# Page1.net
KiCad netlist of a schematic drawn in Altium Designer
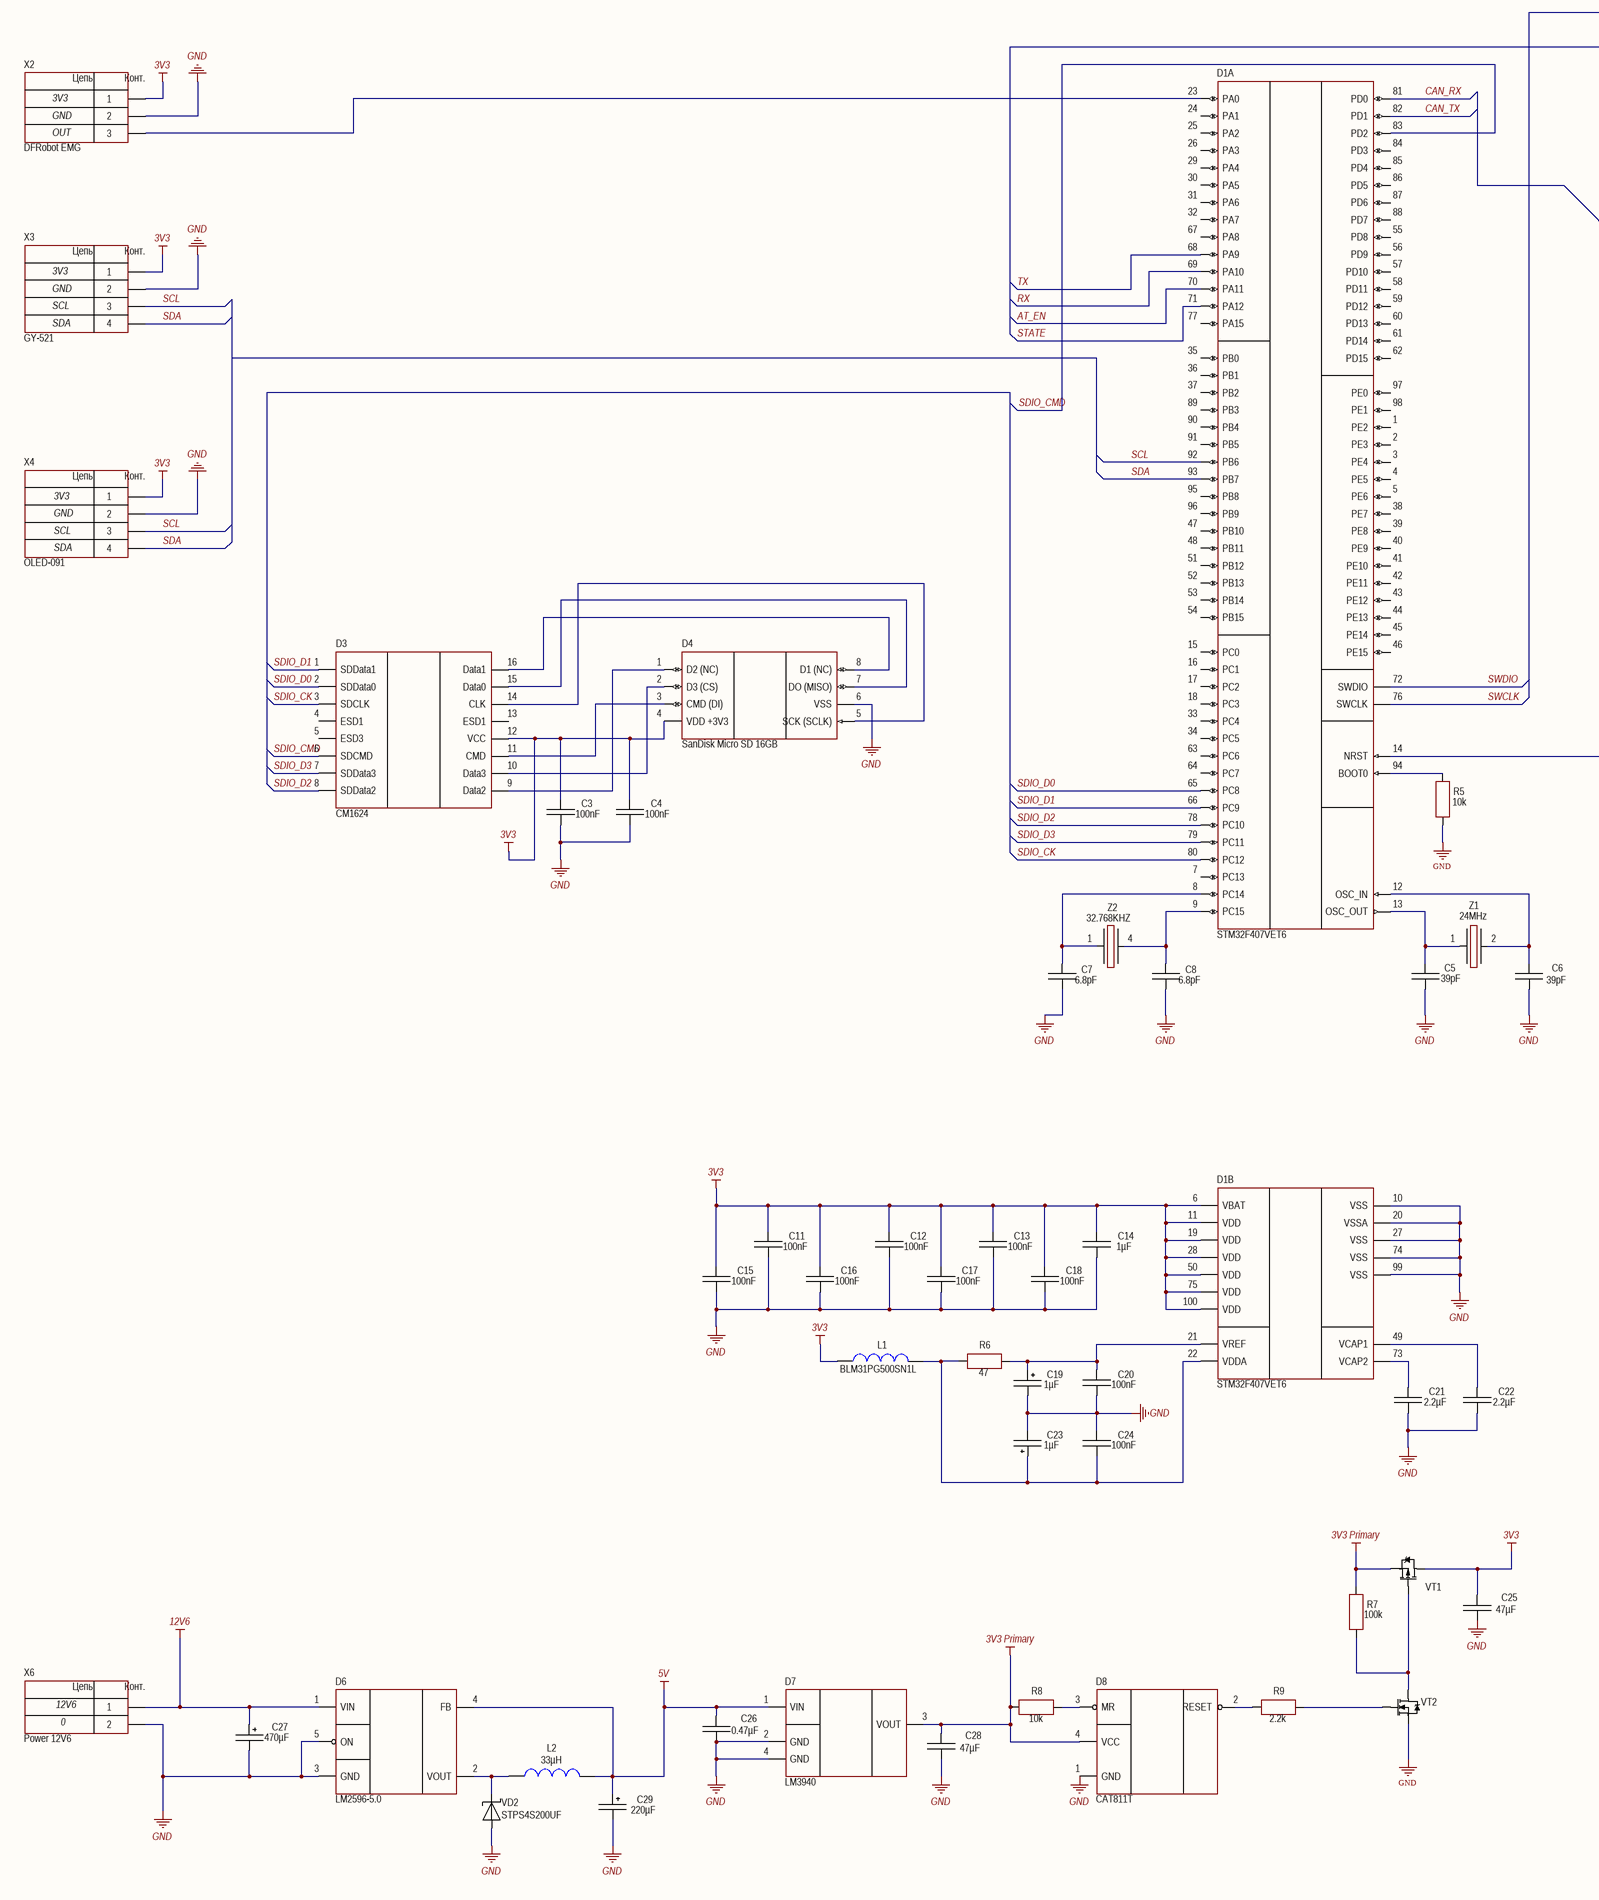
[diagram p0: Page1.SchDoc, left]
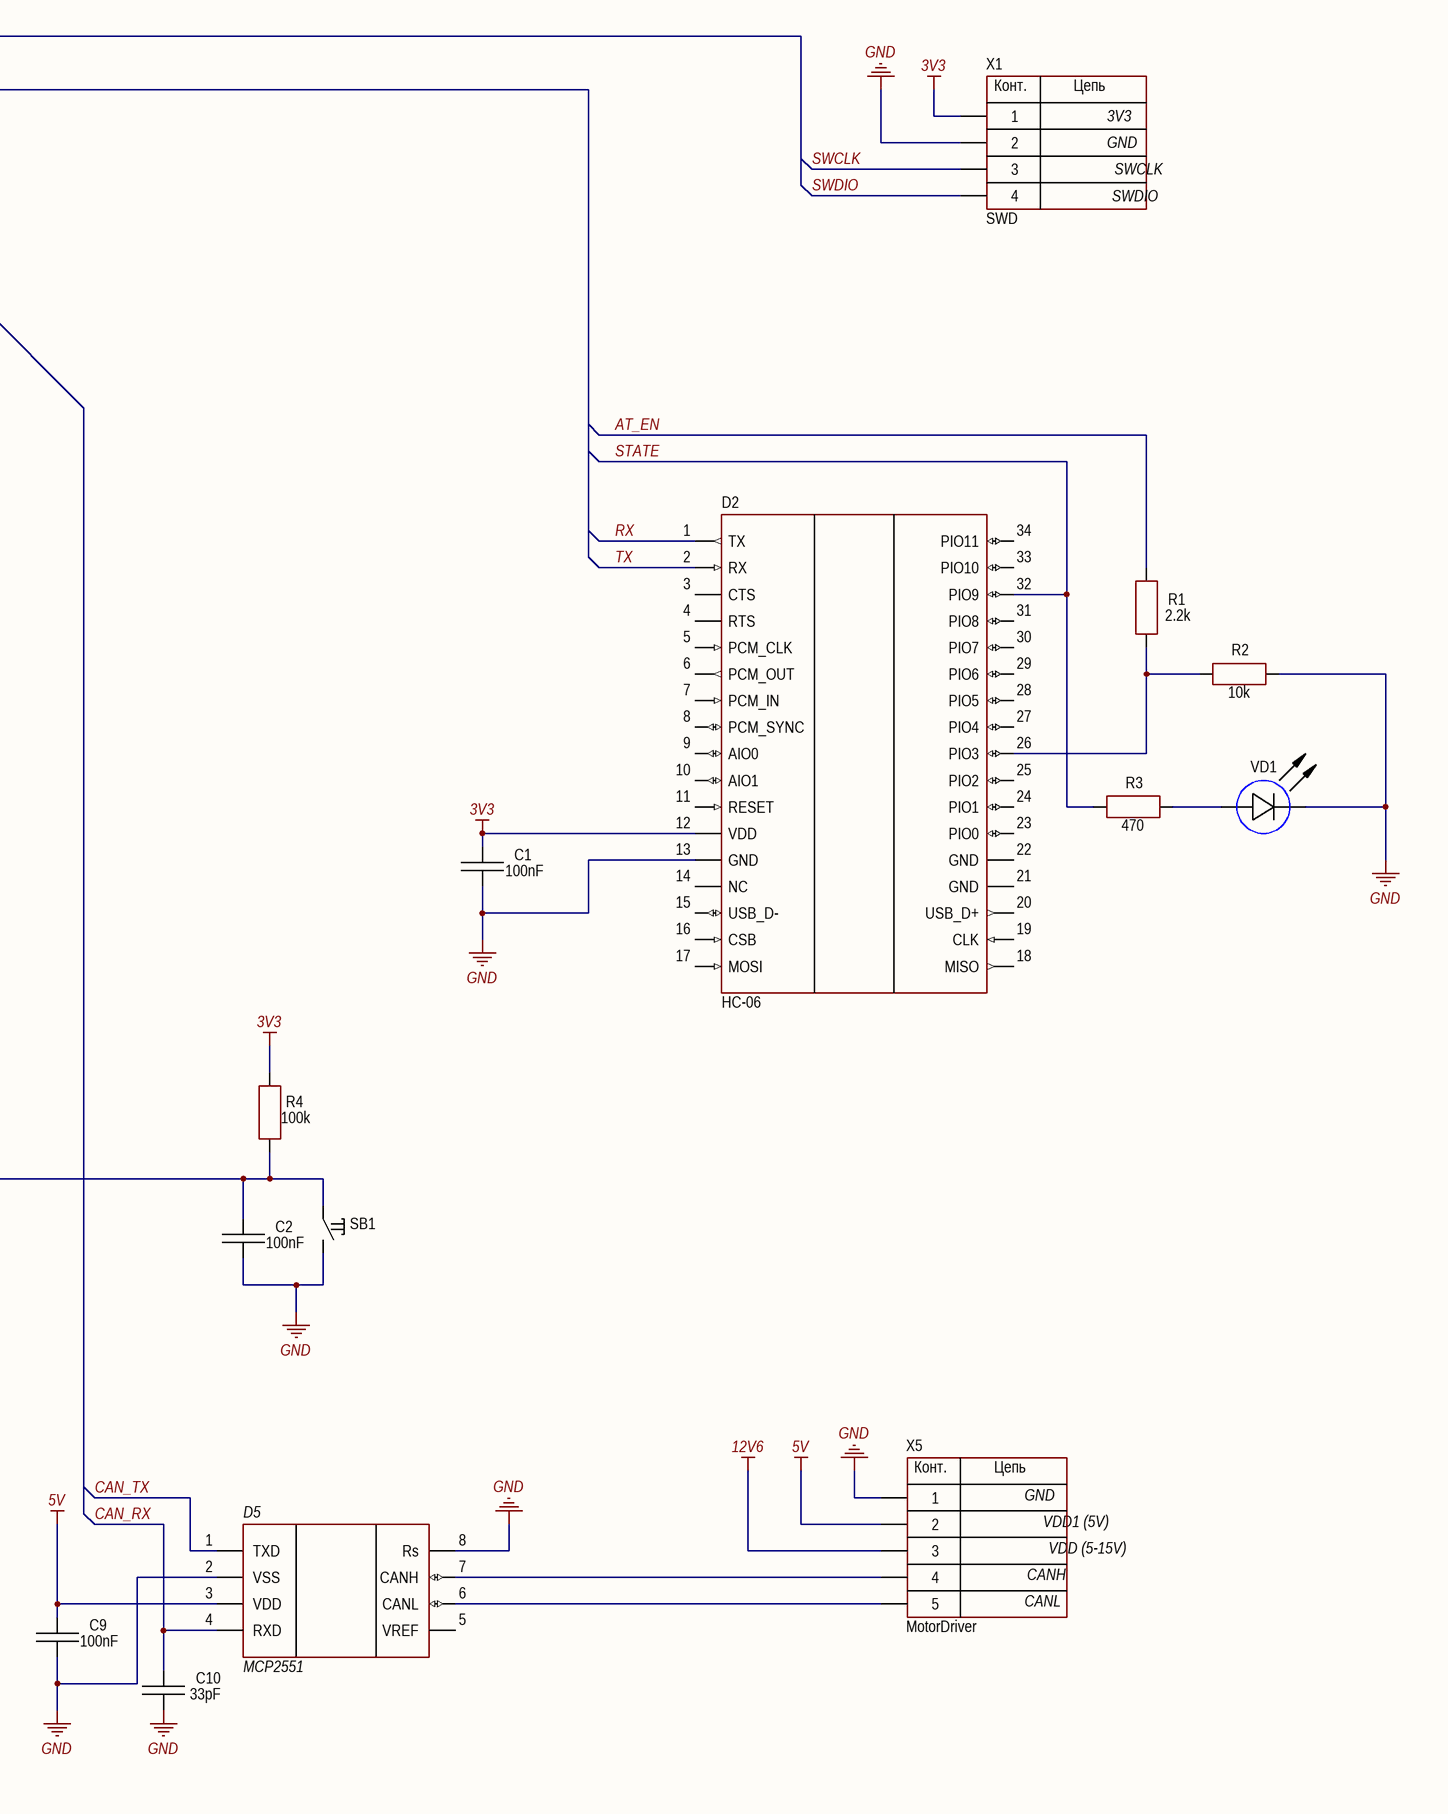
[diagram p1: Page1.SchDoc, right]

(export (version "E")
  (design (tool "Eeschema 10.0.6"))
  (components
    (comp (ref "C1")
      (value "100nF")
      (footprint "CH1206C")
      (fields (field (name "MANUFACTURER") "Murata Electronics North America"))
      (libsource (lib "Discrete") (part "Capacitor"))
    )
    (comp (ref "C2")
      (value "100nF")
      (footprint "CH1206C")
      (fields (field (name "MANUFACTURER") "Murata Electronics North America"))
      (libsource (lib "Discrete") (part "Capacitor"))
    )
    (comp (ref "C3")
      (value "100nF")
      (footprint "CH1206C")
      (fields (field (name "MANUFACTURER") "Murata Electronics North America"))
      (libsource (lib "Discrete") (part "Capacitor"))
    )
    (comp (ref "C4")
      (value "100nF")
      (footprint "CH1206C")
      (fields (field (name "MANUFACTURER") "Murata Electronics North America"))
      (libsource (lib "Discrete") (part "Capacitor"))
    )
    (comp (ref "C5")
      (value "39pF")
      (footprint "CH1206C")
      (fields (field (name "MANUFACTURER") "Murata Electronics North America"))
      (libsource (lib "Discrete") (part "Capacitor"))
    )
    (comp (ref "C6")
      (value "39pF")
      (footprint "CH1206C")
      (fields (field (name "MANUFACTURER") "Murata Electronics North America"))
      (libsource (lib "Discrete") (part "Capacitor"))
    )
    (comp (ref "C7")
      (value "6.8pF")
      (footprint "CH1206C")
      (fields (field (name "MANUFACTURER") "Wurth Electronics Inc."))
      (libsource (lib "Discrete") (part "Capacitor"))
    )
    (comp (ref "C8")
      (value "6.8pF")
      (footprint "CH1206C")
      (fields (field (name "MANUFACTURER") "Wurth Electronics Inc."))
      (libsource (lib "Discrete") (part "Capacitor"))
    )
    (comp (ref "C9")
      (value "100nF")
      (footprint "CH1206C")
      (fields (field (name "MANUFACTURER") "Murata Electronics North America"))
      (libsource (lib "Discrete") (part "Capacitor"))
    )
    (comp (ref "C10")
      (value "33pF")
      (footprint "CH1206C")
      (fields (field (name "MANUFACTURER") "Murata Electronics North America"))
      (libsource (lib "Discrete") (part "Capacitor"))
    )
    (comp (ref "C11")
      (value "100nF")
      (footprint "CH1206C")
      (fields (field (name "MANUFACTURER") "Murata Electronics North America"))
      (libsource (lib "Discrete") (part "Capacitor"))
    )
    (comp (ref "C12")
      (value "100nF")
      (footprint "CH1206C")
      (fields (field (name "MANUFACTURER") "Murata Electronics North America"))
      (libsource (lib "Discrete") (part "Capacitor"))
    )
    (comp (ref "C13")
      (value "100nF")
      (footprint "CH1206C")
      (fields (field (name "MANUFACTURER") "Murata Electronics North America"))
      (libsource (lib "Discrete") (part "Capacitor"))
    )
    (comp (ref "C14")
      (value "1µF")
      (footprint "CH1206C")
      (fields (field (name "MANUFACTURER") "Murata Electronics North America"))
      (libsource (lib "Discrete") (part "Capacitor"))
    )
    (comp (ref "C15")
      (value "100nF")
      (footprint "CH1206C")
      (fields (field (name "MANUFACTURER") "Murata Electronics North America"))
      (libsource (lib "Discrete") (part "Capacitor"))
    )
    (comp (ref "C16")
      (value "100nF")
      (footprint "CH1206C")
      (fields (field (name "MANUFACTURER") "Murata Electronics North America"))
      (libsource (lib "Discrete") (part "Capacitor"))
    )
    (comp (ref "C17")
      (value "100nF")
      (footprint "CH1206C")
      (fields (field (name "MANUFACTURER") "Murata Electronics North America"))
      (libsource (lib "Discrete") (part "Capacitor"))
    )
    (comp (ref "C18")
      (value "100nF")
      (footprint "CH1206C")
      (fields (field (name "MANUFACTURER") "Murata Electronics North America"))
      (libsource (lib "Discrete") (part "Capacitor"))
    )
    (comp (ref "C19")
      (value "1µF")
      (footprint "CAP: Alchip™- MVY")
      (fields (field (name "MANUFACTURER") "United Chemi-Con"))
      (libsource (lib "Discrete") (part "AlumCap"))
    )
    (comp (ref "C20")
      (value "100nF")
      (footprint "CH1206C")
      (fields (field (name "MANUFACTURER") "Murata Electronics North America"))
      (libsource (lib "Discrete") (part "Capacitor"))
    )
    (comp (ref "C21")
      (value "2.2µF")
      (footprint "CH1206C")
      (fields (field (name "MANUFACTURER") "Murata Electronics North America"))
      (libsource (lib "Discrete") (part "Capacitor"))
    )
    (comp (ref "C22")
      (value "2.2µF")
      (footprint "CH1206C")
      (fields (field (name "MANUFACTURER") "Murata Electronics North America"))
      (libsource (lib "Discrete") (part "Capacitor"))
    )
    (comp (ref "C23")
      (value "1µF")
      (footprint "CAP: Alchip™- MVY")
      (fields (field (name "MANUFACTURER") "United Chemi-Con"))
      (libsource (lib "Discrete") (part "AlumCap"))
    )
    (comp (ref "C24")
      (value "100nF")
      (footprint "CH1206C")
      (fields (field (name "MANUFACTURER") "Murata Electronics North America"))
      (libsource (lib "Discrete") (part "Capacitor"))
    )
    (comp (ref "C25")
      (value "47µF")
      (footprint "CH1206C")
      (fields (field (name "MANUFACTURER") "Murata Electronics North America"))
      (libsource (lib "Discrete") (part "Capacitor"))
    )
    (comp (ref "C26")
      (value "0.47µF")
      (footprint "CH1206C")
      (fields (field (name "MANUFACTURER") "Wurth Electronics Inc."))
      (libsource (lib "Discrete") (part "Capacitor"))
    )
    (comp (ref "C27")
      (value "470µF")
      (footprint "CAP: Alchip™- MVY")
      (fields (field (name "MANUFACTURER") "United Chemi-Con"))
      (libsource (lib "Discrete") (part "AlumCap"))
    )
    (comp (ref "C28")
      (value "47µF")
      (footprint "CH1206C")
      (fields (field (name "MANUFACTURER") "Murata Electronics North America"))
      (libsource (lib "Discrete") (part "Capacitor"))
    )
    (comp (ref "C29")
      (value "220µF")
      (footprint "CAP: Alchip™- MVY")
      (fields (field (name "MANUFACTURER") "United Chemi-Con"))
      (libsource (lib "Discrete") (part "AlumCap"))
    )
    (comp (ref "D1")
      (value "STM32F407VET6")
      (footprint "100-LQFP")
      (description "Cortex-M4")
      (fields (field (name "MANUFACTURER") "STMicroelectronics"))
      (libsource (lib "Digital") (part "STM32F407VET6"))
    )
    (comp (ref "D2")
      (value "HC-06")
      (footprint "MOD: HC-05")
      (description "Bluetooth")
      (fields (field (name "MANUFACTURER") "China"))
      (libsource (lib "Module") (part "HC-06"))
    )
    (comp (ref "D3")
      (value "CM1624")
      (description "EMI Filter for T-Flash")
      (fields (field (name "MANUFACTURER") "ON Semiconductor"))
      (libsource (lib "Power Supplies") (part "CM1624"))
    )
    (comp (ref "D4")
      (value "SanDisk Micro SD 16GB")
      (description "Flash")
      (fields (field (name "MANUFACTURER") "SanDisk"))
      (libsource (lib "Digital") (part "MicroSD"))
    )
    (comp (ref "D5")
      (value "MCP2551")
      (footprint "SOT23-8")
      (description "CAN Transceiver")
      (fields (field (name "MANUFACTURER") "China"))
      (libsource (lib "Digital") (part "MCP2551"))
    )
    (comp (ref "D6")
      (value "LM2596-5.0")
      (footprint "D2PAK-5")
      (description "LDO")
      (fields (field (name "MANUFACTURER") "ON Semiconductor"))
      (libsource (lib "Power Supplies") (part "LM2596"))
    )
    (comp (ref "D7")
      (value "LM3940")
      (footprint "SOT223")
      (description "LDO")
      (libsource (lib "Power Supplies") (part "LM3940"))
    )
    (comp (ref "D8")
      (value "CAT811T")
      (description "Power Supply Supervisor")
      (fields (field (name "MANUFACTURER") "ON Semiconductor"))
      (libsource (lib "Power Supplies") (part "CAT811T"))
    )
    (comp (ref "L1")
      (value "BLM31PG500SN1L")
      (footprint "C1206")
      (fields (field (name "MANUFACTURER") "Murata Electronics North America"))
      (libsource (lib "Discrete") (part "Inductor"))
    )
    (comp (ref "L2")
      (value "33µH")
      (footprint "IND: CDRH127")
      (fields (field (name "MANUFACTURER") "Wurth Electronics Inc."))
      (libsource (lib "Discrete") (part "Inductor"))
    )
    (comp (ref "R1")
      (value "2.2k")
      (footprint "CH1206R")
      (fields (field (name "MANUFACTURER") "Panasonic Electronic Components"))
      (libsource (lib "Discrete") (part "Resistor"))
    )
    (comp (ref "R2")
      (value "10k")
      (footprint "CH1206R")
      (fields (field (name "MANUFACTURER") "Stackpole Electronics Inc"))
      (libsource (lib "") (part "Resistor_1"))
    )
    (comp (ref "R3")
      (value "470")
      (footprint "CH1206R")
      (fields (field (name "MANUFACTURER") "Stackpole Electronics Inc"))
      (libsource (lib "") (part "Resistor_1"))
    )
    (comp (ref "R4")
      (value "100k")
      (footprint "CH1206R")
      (fields (field (name "MANUFACTURER") "Stackpole Electronics Inc"))
      (libsource (lib "Discrete") (part "Resistor"))
    )
    (comp (ref "R5")
      (value "10k")
      (footprint "CH0201R")
      (fields (field (name "MANUFACTURER") "Stackpole Electronics Inc"))
      (libsource (lib "Discrete") (part "Resistor"))
    )
    (comp (ref "R6")
      (value "47")
      (footprint "CH1206R")
      (fields (field (name "MANUFACTURER") "Stackpole Electronics Inc"))
      (libsource (lib "") (part "Resistor_1"))
    )
    (comp (ref "R7")
      (value "100k")
      (footprint "CH0201R")
      (fields (field (name "MANUFACTURER") "Stackpole Electronics Inc"))
      (libsource (lib "Discrete") (part "Resistor"))
    )
    (comp (ref "R8")
      (value "10k")
      (footprint "CH0201R")
      (fields (field (name "MANUFACTURER") "Stackpole Electronics Inc"))
      (libsource (lib "") (part "Resistor_1"))
    )
    (comp (ref "R9")
      (value "2.2k")
      (footprint "CH0201R")
      (fields (field (name "MANUFACTURER") "Panasonic Electronic Components"))
      (libsource (lib "") (part "Resistor_1"))
    )
    (comp (ref "SB1")
      (value "~")
      (footprint "BUT: 6x6")
      (description "6x6 mm")
      (fields (field (name "MANUFACTURER") "C&K"))
      (libsource (lib "Connectors") (part "Tactile switches"))
    )
    (comp (ref "VD1")
      (value "~")
      (footprint "CH1206LG")
      (fields (field (name "MANUFACTURER") "QT Brightek (QTB)"))
      (libsource (lib "Discrete") (part "LED"))
    )
    (comp (ref "VD2")
      (value "STPS4S200UF")
      (footprint "DO221AA")
      (fields (field (name "MANUFACTURER") "STMicroelectronics"))
      (libsource (lib "Diods") (part "Diod Schottky"))
    )
    (comp (ref "VT1")
      (value "SI2329DS-T1-GE3")
      (footprint "SOT23_321")
      (description "Mosfet")
      (fields (field (name "MANUFACTURER") "Vishay Siliconix"))
      (libsource (lib "Transistor") (part "P-chanel"))
    )
    (comp (ref "VT2")
      (value "SI2342DS-T1-GE3")
      (footprint "SOT23_321")
      (description "Mosfet")
      (fields (field (name "MANUFACTURER") "Vishay Siliconix"))
      (libsource (lib "Transistor") (part "N-chanel"))
    )
    (comp (ref "X1")
      (value "SWD")
      (footprint "CON: 0533750410")
      (fields (field (name "MANUFACTURER") "Molex"))
      (libsource (lib "") (part "4-Connector_1"))
    )
    (comp (ref "X2")
      (value "DFRobot EMG")
      (footprint "CON: 0533750310")
      (fields (field (name "MANUFACTURER") "Molex"))
      (libsource (lib "Connectors") (part "3-Connector"))
    )
    (comp (ref "X3")
      (value "GY-521")
      (footprint "CON: 0533750410")
      (fields (field (name "MANUFACTURER") "Molex"))
      (libsource (lib "Connectors") (part "4-Connector"))
    )
    (comp (ref "X4")
      (value "OLED-091")
      (footprint "CON: 0533750410")
      (fields (field (name "MANUFACTURER") "Molex"))
      (libsource (lib "Connectors") (part "4-Connector"))
    )
    (comp (ref "X5")
      (value "MotorDriver")
      (footprint "CON: 0533750510")
      (fields (field (name "MANUFACTURER") "Molex"))
      (libsource (lib "Connectors") (part "5-Connector"))
    )
    (comp (ref "X6")
      (value "Power 12V6")
      (footprint "CON: 0533750210")
      (fields (field (name "MANUFACTURER") "Molex"))
      (libsource (lib "Connectors") (part "2-Connector"))
    )
    (comp (ref "Z1")
      (value "24MHz")
      (footprint "OSC: 5032")
      (fields (field (name "MANUFACTURER") "Abracon LLC"))
      (libsource (lib "") (part "Oscillator_1"))
    )
    (comp (ref "Z2")
      (value "32.768KHZ")
      (footprint "OSC: 2520")
      (fields (field (name "MANUFACTURER") "Epson Toyocom"))
      (libsource (lib "Discrete") (part "Oscillator"))
    )
  )
  (nets
    (net (code "1") (name "/AT_EN") (class "Default")
      (node (ref "D1") (pin "70") (pinfunction "PA11_70") (pintype "bidirectional"))
      (node (ref "R1") (pin "2") (pinfunction "2_2") (pintype "passive"))
    )
    (net (code "2") (name "/CAN_RX") (class "Default")
      (node (ref "C10") (pin "2") (pinfunction "2_2") (pintype "power_in"))
      (node (ref "D1") (pin "81") (pinfunction "PD0_81") (pintype "bidirectional"))
      (node (ref "D5") (pin "4") (pinfunction "RXD_4") (pintype "passive"))
    )
    (net (code "3") (name "/CAN_TX") (class "Default")
      (node (ref "D1") (pin "82") (pinfunction "PD1_82") (pintype "bidirectional"))
      (node (ref "D5") (pin "1") (pinfunction "TXD_1") (pintype "passive"))
    )
    (net (code "4") (name "/RX") (class "Default")
      (node (ref "D1") (pin "69") (pinfunction "PA10_69") (pintype "bidirectional"))
      (node (ref "D2") (pin "1") (pinfunction "TX_1") (pintype "output"))
    )
    (net (code "5") (name "/SCL") (class "Default")
      (node (ref "D1") (pin "92") (pinfunction "PB6_92") (pintype "bidirectional"))
      (node (ref "X3") (pin "3") (pinfunction "3_3") (pintype "power_in"))
      (node (ref "X4") (pin "3") (pinfunction "3_3") (pintype "power_in"))
    )
    (net (code "6") (name "/SDA") (class "Default")
      (node (ref "D1") (pin "93") (pinfunction "PB7_93") (pintype "bidirectional"))
      (node (ref "X3") (pin "4") (pinfunction "4_4") (pintype "power_in"))
      (node (ref "X4") (pin "4") (pinfunction "4_4") (pintype "power_in"))
    )
    (net (code "7") (name "/SDIO_CK") (class "Default")
      (node (ref "D1") (pin "80") (pinfunction "PC12_80") (pintype "bidirectional"))
      (node (ref "D3") (pin "3") (pinfunction "SDCLK_3") (pintype "passive"))
    )
    (net (code "8") (name "/SDIO_CMD") (class "Default")
      (node (ref "D1") (pin "83") (pinfunction "PD2_83") (pintype "bidirectional"))
      (node (ref "D3") (pin "6") (pinfunction "SDCMD_6") (pintype "passive"))
    )
    (net (code "9") (name "/SDIO_D0") (class "Default")
      (node (ref "D1") (pin "65") (pinfunction "PC8_65") (pintype "bidirectional"))
      (node (ref "D3") (pin "2") (pinfunction "SDData0_2") (pintype "passive"))
    )
    (net (code "10") (name "/SDIO_D1") (class "Default")
      (node (ref "D1") (pin "66") (pinfunction "PC9_66") (pintype "bidirectional"))
      (node (ref "D3") (pin "1") (pinfunction "SDData1_1") (pintype "passive"))
    )
    (net (code "11") (name "/SDIO_D2") (class "Default")
      (node (ref "D1") (pin "78") (pinfunction "PC10_78") (pintype "bidirectional"))
      (node (ref "D3") (pin "8") (pinfunction "SDData2_8") (pintype "passive"))
    )
    (net (code "12") (name "/SDIO_D3") (class "Default")
      (node (ref "D1") (pin "79") (pinfunction "PC11_79") (pintype "bidirectional"))
      (node (ref "D3") (pin "7") (pinfunction "SDData3_7") (pintype "passive"))
    )
    (net (code "13") (name "/STATE") (class "Default")
      (node (ref "D1") (pin "71") (pinfunction "PA12_71") (pintype "bidirectional"))
      (node (ref "D2") (pin "32") (pinfunction "PIO9_32") (pintype "bidirectional"))
      (node (ref "R3") (pin "1") (pinfunction "1_1") (pintype "passive"))
    )
    (net (code "14") (name "/SWCLK") (class "Default")
      (node (ref "D1") (pin "76") (pinfunction "SWCLK_76") (pintype "passive"))
      (node (ref "X1") (pin "3") (pinfunction "3_3") (pintype "power_in"))
    )
    (net (code "15") (name "/SWDIO") (class "Default")
      (node (ref "D1") (pin "72") (pinfunction "SWDIO_72") (pintype "passive"))
      (node (ref "X1") (pin "4") (pinfunction "4_4") (pintype "power_in"))
    )
    (net (code "16") (name "/TX") (class "Default")
      (node (ref "D1") (pin "68") (pinfunction "PA9_68") (pintype "bidirectional"))
      (node (ref "D2") (pin "2") (pinfunction "RX_2") (pintype "input"))
    )
    (net (code "17") (name "3V3") (class "Default")
      (node (ref "C1") (pin "2") (pinfunction "2_2") (pintype "power_in"))
      (node (ref "C11") (pin "2") (pinfunction "2_2") (pintype "power_in"))
      (node (ref "C12") (pin "2") (pinfunction "2_2") (pintype "power_in"))
      (node (ref "C13") (pin "2") (pinfunction "2_2") (pintype "power_in"))
      (node (ref "C14") (pin "2") (pinfunction "2_2") (pintype "power_in"))
      (node (ref "C15") (pin "2") (pinfunction "2_2") (pintype "power_in"))
      (node (ref "C16") (pin "2") (pinfunction "2_2") (pintype "power_in"))
      (node (ref "C17") (pin "2") (pinfunction "2_2") (pintype "power_in"))
      (node (ref "C18") (pin "2") (pinfunction "2_2") (pintype "power_in"))
      (node (ref "C25") (pin "1") (pinfunction "1_1") (pintype "power_in"))
      (node (ref "C3") (pin "2") (pinfunction "2_2") (pintype "power_in"))
      (node (ref "C4") (pin "2") (pinfunction "2_2") (pintype "power_in"))
      (node (ref "D1") (pin "100") (pinfunction "VDD_100") (pintype "power_in"))
      (node (ref "D1") (pin "11") (pinfunction "VDD_11") (pintype "power_in"))
      (node (ref "D1") (pin "19") (pinfunction "VDD_19") (pintype "power_in"))
      (node (ref "D1") (pin "28") (pinfunction "VDD_28") (pintype "power_in"))
      (node (ref "D1") (pin "50") (pinfunction "VDD_50") (pintype "power_in"))
      (node (ref "D1") (pin "6") (pinfunction "VBAT_6") (pintype "power_in"))
      (node (ref "D1") (pin "75") (pinfunction "VDD_75") (pintype "power_in"))
      (node (ref "D2") (pin "12") (pinfunction "VDD_12") (pintype "passive"))
      (node (ref "D3") (pin "12") (pinfunction "VCC_12") (pintype "passive"))
      (node (ref "D4") (pin "4") (pinfunction "VDD_+3V3_4") (pintype "power_in"))
      (node (ref "L1") (pin "2") (pinfunction "2_2") (pintype "passive"))
      (node (ref "R4") (pin "2") (pinfunction "2_2") (pintype "passive"))
      (node (ref "VT1") (pin "2") (pinfunction "D_2") (pintype "passive"))
      (node (ref "X1") (pin "1") (pinfunction "1_1") (pintype "passive"))
      (node (ref "X2") (pin "1") (pinfunction "1_1") (pintype "passive"))
      (node (ref "X3") (pin "1") (pinfunction "1_1") (pintype "passive"))
      (node (ref "X4") (pin "1") (pinfunction "1_1") (pintype "passive"))
    )
    (net (code "18") (name "3V3 Primary") (class "Default")
      (node (ref "C28") (pin "1") (pinfunction "1_1") (pintype "power_in"))
      (node (ref "D7") (pin "3") (pinfunction "VOUT_3") (pintype "power_in"))
      (node (ref "D8") (pin "4") (pinfunction "VCC_4") (pintype "power_in"))
      (node (ref "R7") (pin "2") (pinfunction "2_2") (pintype "passive"))
      (node (ref "R8") (pin "1") (pinfunction "1_1") (pintype "passive"))
      (node (ref "VT1") (pin "3") (pinfunction "S_3") (pintype "passive"))
    )
    (net (code "19") (name "5V") (class "Default")
      (node (ref "C26") (pin "1") (pinfunction "1_1") (pintype "power_in"))
      (node (ref "C29") (pin "1") (pinfunction "1_1") (pintype "power_in"))
      (node (ref "C9") (pin "2") (pinfunction "2_2") (pintype "power_in"))
      (node (ref "D5") (pin "3") (pinfunction "VDD_3") (pintype "power_in"))
      (node (ref "D6") (pin "4") (pinfunction "FB_4") (pintype "power_in"))
      (node (ref "D7") (pin "1") (pinfunction "VIN_1") (pintype "power_in"))
      (node (ref "L2") (pin "1") (pinfunction "1_1") (pintype "passive"))
      (node (ref "X5") (pin "2") (pinfunction "2_2") (pintype "passive"))
    )
    (net (code "20") (name "12V6") (class "Default")
      (node (ref "C27") (pin "1") (pinfunction "1_1") (pintype "power_in"))
      (node (ref "D6") (pin "1") (pinfunction "VIN_1") (pintype "power_in"))
      (node (ref "X5") (pin "3") (pinfunction "3_3") (pintype "power_in"))
      (node (ref "X6") (pin "1") (pinfunction "1_1") (pintype "passive"))
    )
    (net (code "21") (name "GND") (class "Default")
      (node (ref "C1") (pin "1") (pinfunction "1_1") (pintype "power_in"))
      (node (ref "C10") (pin "1") (pinfunction "1_1") (pintype "power_in"))
      (node (ref "C11") (pin "1") (pinfunction "1_1") (pintype "power_in"))
      (node (ref "C12") (pin "1") (pinfunction "1_1") (pintype "power_in"))
      (node (ref "C13") (pin "1") (pinfunction "1_1") (pintype "power_in"))
      (node (ref "C14") (pin "1") (pinfunction "1_1") (pintype "power_in"))
      (node (ref "C15") (pin "1") (pinfunction "1_1") (pintype "power_in"))
      (node (ref "C16") (pin "1") (pinfunction "1_1") (pintype "power_in"))
      (node (ref "C17") (pin "1") (pinfunction "1_1") (pintype "power_in"))
      (node (ref "C18") (pin "1") (pinfunction "1_1") (pintype "power_in"))
      (node (ref "C19") (pin "2") (pinfunction "2_2") (pintype "power_in"))
      (node (ref "C2") (pin "1") (pinfunction "1_1") (pintype "power_in"))
      (node (ref "C20") (pin "1") (pinfunction "1_1") (pintype "power_in"))
      (node (ref "C21") (pin "1") (pinfunction "1_1") (pintype "power_in"))
      (node (ref "C22") (pin "1") (pinfunction "1_1") (pintype "power_in"))
      (node (ref "C23") (pin "2") (pinfunction "2_2") (pintype "power_in"))
      (node (ref "C24") (pin "2") (pinfunction "2_2") (pintype "power_in"))
      (node (ref "C25") (pin "2") (pinfunction "2_2") (pintype "power_in"))
      (node (ref "C26") (pin "2") (pinfunction "2_2") (pintype "power_in"))
      (node (ref "C27") (pin "2") (pinfunction "2_2") (pintype "power_in"))
      (node (ref "C28") (pin "2") (pinfunction "2_2") (pintype "power_in"))
      (node (ref "C29") (pin "2") (pinfunction "2_2") (pintype "power_in"))
      (node (ref "C3") (pin "1") (pinfunction "1_1") (pintype "power_in"))
      (node (ref "C4") (pin "1") (pinfunction "1_1") (pintype "power_in"))
      (node (ref "C5") (pin "1") (pinfunction "1_1") (pintype "power_in"))
      (node (ref "C6") (pin "1") (pinfunction "1_1") (pintype "power_in"))
      (node (ref "C7") (pin "1") (pinfunction "1_1") (pintype "power_in"))
      (node (ref "C8") (pin "1") (pinfunction "1_1") (pintype "power_in"))
      (node (ref "C9") (pin "1") (pinfunction "1_1") (pintype "power_in"))
      (node (ref "D1") (pin "10") (pinfunction "VSS_10") (pintype "power_in"))
      (node (ref "D1") (pin "20") (pinfunction "VSSA_20") (pintype "power_in"))
      (node (ref "D1") (pin "27") (pinfunction "VSS_27") (pintype "power_in"))
      (node (ref "D1") (pin "74") (pinfunction "VSS_74") (pintype "power_in"))
      (node (ref "D1") (pin "99") (pinfunction "VSS_99") (pintype "power_in"))
      (node (ref "D2") (pin "13") (pinfunction "GND_13") (pintype "passive"))
      (node (ref "D4") (pin "6") (pinfunction "VSS_6") (pintype "power_in"))
      (node (ref "D5") (pin "2") (pinfunction "VSS_2") (pintype "power_in"))
      (node (ref "D5") (pin "8") (pinfunction "Rs_8") (pintype "passive"))
      (node (ref "D6") (pin "3") (pinfunction "GND_3") (pintype "power_in"))
      (node (ref "D6") (pin "5") (pinfunction "ON_5") (pintype "power_in"))
      (node (ref "D7") (pin "2") (pinfunction "GND_2") (pintype "power_in"))
      (node (ref "D7") (pin "4") (pinfunction "GND_4") (pintype "power_in"))
      (node (ref "D8") (pin "1") (pinfunction "GND_1") (pintype "power_in"))
      (node (ref "R2") (pin "2") (pinfunction "2_2") (pintype "passive"))
      (node (ref "R5") (pin "1") (pinfunction "1_1") (pintype "passive"))
      (node (ref "SB1") (pin "2") (pinfunction "2_2") (pintype "passive"))
      (node (ref "VD1") (pin "2") (pinfunction "C_2") (pintype "passive"))
      (node (ref "VD2") (pin "1") (pinfunction "1_1") (pintype "passive"))
      (node (ref "VT2") (pin "3") (pinfunction "S_3") (pintype "passive"))
      (node (ref "X1") (pin "2") (pinfunction "2_2") (pintype "passive"))
      (node (ref "X2") (pin "2") (pinfunction "2_2") (pintype "passive"))
      (node (ref "X3") (pin "2") (pinfunction "2_2") (pintype "passive"))
      (node (ref "X4") (pin "2") (pinfunction "2_2") (pintype "passive"))
      (node (ref "X5") (pin "1") (pinfunction "1_1") (pintype "passive"))
      (node (ref "X6") (pin "2") (pinfunction "2_2") (pintype "passive"))
    )
    (net (code "22") (name "Net-(D1A-BOOT0)") (class "Default")
      (node (ref "D1") (pin "94") (pinfunction "BOOT0_94") (pintype "input"))
      (node (ref "R5") (pin "2") (pinfunction "2_2") (pintype "passive"))
    )
    (net (code "23") (name "Net-(D1A-NRST)") (class "Default")
      (node (ref "C2") (pin "2") (pinfunction "2_2") (pintype "power_in"))
      (node (ref "D1") (pin "14") (pinfunction "NRST_14") (pintype "input"))
      (node (ref "R4") (pin "1") (pinfunction "1_1") (pintype "passive"))
      (node (ref "SB1") (pin "1") (pinfunction "1_1") (pintype "passive"))
    )
    (net (code "24") (name "Net-(D1A-OSC_IN)") (class "Default")
      (node (ref "C6") (pin "2") (pinfunction "2_2") (pintype "power_in"))
      (node (ref "D1") (pin "12") (pinfunction "OSC_IN_12") (pintype "input"))
      (node (ref "Z1") (pin "2") (pinfunction "2_2") (pintype "passive"))
    )
    (net (code "25") (name "Net-(D1A-OSC_OUT)") (class "Default")
      (node (ref "C5") (pin "2") (pinfunction "2_2") (pintype "power_in"))
      (node (ref "D1") (pin "13") (pinfunction "OSC_OUT_13") (pintype "output"))
      (node (ref "Z1") (pin "1") (pinfunction "1_1") (pintype "passive"))
    )
    (net (code "26") (name "Net-(D1A-PA0)") (class "Default")
      (node (ref "D1") (pin "23") (pinfunction "PA0_23") (pintype "bidirectional"))
      (node (ref "X2") (pin "3") (pinfunction "3_3") (pintype "power_in"))
    )
    (net (code "27") (name "Net-(D1A-PC14)") (class "Default")
      (node (ref "C7") (pin "2") (pinfunction "2_2") (pintype "power_in"))
      (node (ref "D1") (pin "8") (pinfunction "PC14_8") (pintype "bidirectional"))
      (node (ref "Z2") (pin "1") (pinfunction "1_1") (pintype "passive"))
    )
    (net (code "28") (name "Net-(D1A-PC15)") (class "Default")
      (node (ref "C8") (pin "2") (pinfunction "2_2") (pintype "power_in"))
      (node (ref "D1") (pin "9") (pinfunction "PC15_9") (pintype "bidirectional"))
      (node (ref "Z2") (pin "4") (pinfunction "4_4") (pintype "passive"))
    )
    (net (code "29") (name "Net-(D1B-VCAP1)") (class "Default")
      (node (ref "C22") (pin "2") (pinfunction "2_2") (pintype "power_in"))
      (node (ref "D1") (pin "49") (pinfunction "VCAP1_49") (pintype "power_in"))
    )
    (net (code "30") (name "Net-(D1B-VCAP2)") (class "Default")
      (node (ref "C21") (pin "2") (pinfunction "2_2") (pintype "power_in"))
      (node (ref "D1") (pin "73") (pinfunction "VCAP2_73") (pintype "power_in"))
    )
    (net (code "31") (name "Net-(D1B-VDDA)") (class "Default")
      (node (ref "C23") (pin "1") (pinfunction "1_1") (pintype "power_in"))
      (node (ref "C24") (pin "1") (pinfunction "1_1") (pintype "power_in"))
      (node (ref "D1") (pin "22") (pinfunction "VDDA_22") (pintype "power_in"))
      (node (ref "L1") (pin "1") (pinfunction "1_1") (pintype "passive"))
      (node (ref "R6") (pin "1") (pinfunction "1_1") (pintype "passive"))
    )
    (net (code "32") (name "Net-(D1B-VREF)") (class "Default")
      (node (ref "C19") (pin "1") (pinfunction "1_1") (pintype "power_in"))
      (node (ref "C20") (pin "2") (pinfunction "2_2") (pintype "power_in"))
      (node (ref "D1") (pin "21") (pinfunction "VREF_21") (pintype "power_in"))
      (node (ref "R6") (pin "2") (pinfunction "2_2") (pintype "passive"))
    )
    (net (code "33") (name "Net-(D2-PIO3)") (class "Default")
      (node (ref "D2") (pin "26") (pinfunction "PIO3_26") (pintype "bidirectional"))
      (node (ref "R1") (pin "1") (pinfunction "1_1") (pintype "passive"))
      (node (ref "R2") (pin "1") (pinfunction "1_1") (pintype "passive"))
    )
    (net (code "34") (name "Net-(D3-CLK)") (class "Default")
      (node (ref "D3") (pin "14") (pinfunction "CLK_14") (pintype "passive"))
      (node (ref "D4") (pin "5") (pinfunction "SCK_(SCLK)_5") (pintype "input"))
    )
    (net (code "35") (name "Net-(D3-CMD)") (class "Default")
      (node (ref "D3") (pin "11") (pinfunction "CMD_11") (pintype "passive"))
      (node (ref "D4") (pin "3") (pinfunction "CMD_(DI)_3") (pintype "bidirectional"))
    )
    (net (code "36") (name "Net-(D3-Data0)") (class "Default")
      (node (ref "D3") (pin "15") (pinfunction "Data0_15") (pintype "passive"))
      (node (ref "D4") (pin "7") (pinfunction "DO_(MISO)_7") (pintype "bidirectional"))
    )
    (net (code "37") (name "Net-(D3-Data1)") (class "Default")
      (node (ref "D3") (pin "16") (pinfunction "Data1_16") (pintype "passive"))
      (node (ref "D4") (pin "8") (pinfunction "D1_(NC)_8") (pintype "bidirectional"))
    )
    (net (code "38") (name "Net-(D3-Data2)") (class "Default")
      (node (ref "D3") (pin "9") (pinfunction "Data2_9") (pintype "passive"))
      (node (ref "D4") (pin "1") (pinfunction "D2_(NC)_1") (pintype "bidirectional"))
    )
    (net (code "39") (name "Net-(D3-Data3)") (class "Default")
      (node (ref "D3") (pin "10") (pinfunction "Data3_10") (pintype "passive"))
      (node (ref "D4") (pin "2") (pinfunction "D3_(CS)_2") (pintype "bidirectional"))
    )
    (net (code "40") (name "Net-(D5-CANH)") (class "Default")
      (node (ref "D5") (pin "7") (pinfunction "CANH_7") (pintype "bidirectional"))
      (node (ref "X5") (pin "4") (pinfunction "4_4") (pintype "power_in"))
    )
    (net (code "41") (name "Net-(D5-CANL)") (class "Default")
      (node (ref "D5") (pin "6") (pinfunction "CANL_6") (pintype "bidirectional"))
      (node (ref "X5") (pin "5") (pinfunction "5_5") (pintype "power_in"))
    )
    (net (code "42") (name "Net-(D6-VOUT)") (class "Default")
      (node (ref "D6") (pin "2") (pinfunction "VOUT_2") (pintype "power_in"))
      (node (ref "L2") (pin "2") (pinfunction "2_2") (pintype "passive"))
      (node (ref "VD2") (pin "2") (pinfunction "2_2") (pintype "passive"))
    )
    (net (code "43") (name "Net-(D8-MR)") (class "Default")
      (node (ref "D8") (pin "3") (pinfunction "MR_3") (pintype "power_in"))
      (node (ref "R8") (pin "2") (pinfunction "2_2") (pintype "passive"))
    )
    (net (code "44") (name "Net-(D8-RESET)") (class "Default")
      (node (ref "D8") (pin "2") (pinfunction "RESET_2") (pintype "power_in"))
      (node (ref "R9") (pin "1") (pinfunction "1_1") (pintype "passive"))
    )
    (net (code "45") (name "Net-(VD1-A)") (class "Default")
      (node (ref "R3") (pin "2") (pinfunction "2_2") (pintype "passive"))
      (node (ref "VD1") (pin "1") (pinfunction "A_1") (pintype "passive"))
    )
    (net (code "46") (name "Net-(VT1-G)") (class "Default")
      (node (ref "R7") (pin "1") (pinfunction "1_1") (pintype "passive"))
      (node (ref "VT1") (pin "1") (pinfunction "G_1") (pintype "passive"))
      (node (ref "VT2") (pin "2") (pinfunction "D_2") (pintype "passive"))
    )
    (net (code "47") (name "Net-(VT2-G)") (class "Default")
      (node (ref "R9") (pin "2") (pinfunction "2_2") (pintype "passive"))
      (node (ref "VT2") (pin "1") (pinfunction "G_1") (pintype "passive"))
    )
    (net (code "48") (name "unconnected-(D1A-PA1-Pad24)") (class "Default")
      (node (ref "D1") (pin "24") (pinfunction "PA1_24") (pintype "bidirectional"))
    )
    (net (code "49") (name "unconnected-(D1A-PA2-Pad25)") (class "Default")
      (node (ref "D1") (pin "25") (pinfunction "PA2_25") (pintype "bidirectional"))
    )
    (net (code "50") (name "unconnected-(D1A-PA3-Pad26)") (class "Default")
      (node (ref "D1") (pin "26") (pinfunction "PA3_26") (pintype "bidirectional"))
    )
    (net (code "51") (name "unconnected-(D1A-PA4-Pad29)") (class "Default")
      (node (ref "D1") (pin "29") (pinfunction "PA4_29") (pintype "bidirectional"))
    )
    (net (code "52") (name "unconnected-(D1A-PA5-Pad30)") (class "Default")
      (node (ref "D1") (pin "30") (pinfunction "PA5_30") (pintype "bidirectional"))
    )
    (net (code "53") (name "unconnected-(D1A-PA6-Pad31)") (class "Default")
      (node (ref "D1") (pin "31") (pinfunction "PA6_31") (pintype "bidirectional"))
    )
    (net (code "54") (name "unconnected-(D1A-PA7-Pad32)") (class "Default")
      (node (ref "D1") (pin "32") (pinfunction "PA7_32") (pintype "bidirectional"))
    )
    (net (code "55") (name "unconnected-(D1A-PA8-Pad67)") (class "Default")
      (node (ref "D1") (pin "67") (pinfunction "PA8_67") (pintype "bidirectional"))
    )
    (net (code "56") (name "unconnected-(D1A-PA15-Pad77)") (class "Default")
      (node (ref "D1") (pin "77") (pinfunction "PA15_77") (pintype "bidirectional"))
    )
    (net (code "57") (name "unconnected-(D1A-PB0-Pad35)") (class "Default")
      (node (ref "D1") (pin "35") (pinfunction "PB0_35") (pintype "bidirectional"))
    )
    (net (code "58") (name "unconnected-(D1A-PB1-Pad36)") (class "Default")
      (node (ref "D1") (pin "36") (pinfunction "PB1_36") (pintype "bidirectional"))
    )
    (net (code "59") (name "unconnected-(D1A-PB2-Pad37)") (class "Default")
      (node (ref "D1") (pin "37") (pinfunction "PB2_37") (pintype "bidirectional"))
    )
    (net (code "60") (name "unconnected-(D1A-PB3-Pad89)") (class "Default")
      (node (ref "D1") (pin "89") (pinfunction "PB3_89") (pintype "bidirectional"))
    )
    (net (code "61") (name "unconnected-(D1A-PB4-Pad90)") (class "Default")
      (node (ref "D1") (pin "90") (pinfunction "PB4_90") (pintype "bidirectional"))
    )
    (net (code "62") (name "unconnected-(D1A-PB5-Pad91)") (class "Default")
      (node (ref "D1") (pin "91") (pinfunction "PB5_91") (pintype "bidirectional"))
    )
    (net (code "63") (name "unconnected-(D1A-PB8-Pad95)") (class "Default")
      (node (ref "D1") (pin "95") (pinfunction "PB8_95") (pintype "bidirectional"))
    )
    (net (code "64") (name "unconnected-(D1A-PB9-Pad96)") (class "Default")
      (node (ref "D1") (pin "96") (pinfunction "PB9_96") (pintype "bidirectional"))
    )
    (net (code "65") (name "unconnected-(D1A-PB10-Pad47)") (class "Default")
      (node (ref "D1") (pin "47") (pinfunction "PB10_47") (pintype "bidirectional"))
    )
    (net (code "66") (name "unconnected-(D1A-PB11-Pad48)") (class "Default")
      (node (ref "D1") (pin "48") (pinfunction "PB11_48") (pintype "bidirectional"))
    )
    (net (code "67") (name "unconnected-(D1A-PB12-Pad51)") (class "Default")
      (node (ref "D1") (pin "51") (pinfunction "PB12_51") (pintype "bidirectional"))
    )
    (net (code "68") (name "unconnected-(D1A-PB13-Pad52)") (class "Default")
      (node (ref "D1") (pin "52") (pinfunction "PB13_52") (pintype "bidirectional"))
    )
    (net (code "69") (name "unconnected-(D1A-PB14-Pad53)") (class "Default")
      (node (ref "D1") (pin "53") (pinfunction "PB14_53") (pintype "bidirectional"))
    )
    (net (code "70") (name "unconnected-(D1A-PB15-Pad54)") (class "Default")
      (node (ref "D1") (pin "54") (pinfunction "PB15_54") (pintype "bidirectional"))
    )
    (net (code "71") (name "unconnected-(D1A-PC0-Pad15)") (class "Default")
      (node (ref "D1") (pin "15") (pinfunction "PC0_15") (pintype "bidirectional"))
    )
    (net (code "72") (name "unconnected-(D1A-PC1-Pad16)") (class "Default")
      (node (ref "D1") (pin "16") (pinfunction "PC1_16") (pintype "bidirectional"))
    )
    (net (code "73") (name "unconnected-(D1A-PC2-Pad17)") (class "Default")
      (node (ref "D1") (pin "17") (pinfunction "PC2_17") (pintype "bidirectional"))
    )
    (net (code "74") (name "unconnected-(D1A-PC3-Pad18)") (class "Default")
      (node (ref "D1") (pin "18") (pinfunction "PC3_18") (pintype "bidirectional"))
    )
    (net (code "75") (name "unconnected-(D1A-PC4-Pad33)") (class "Default")
      (node (ref "D1") (pin "33") (pinfunction "PC4_33") (pintype "bidirectional"))
    )
    (net (code "76") (name "unconnected-(D1A-PC5-Pad34)") (class "Default")
      (node (ref "D1") (pin "34") (pinfunction "PC5_34") (pintype "bidirectional"))
    )
    (net (code "77") (name "unconnected-(D1A-PC6-Pad63)") (class "Default")
      (node (ref "D1") (pin "63") (pinfunction "PC6_63") (pintype "bidirectional"))
    )
    (net (code "78") (name "unconnected-(D1A-PC7-Pad64)") (class "Default")
      (node (ref "D1") (pin "64") (pinfunction "PC7_64") (pintype "bidirectional"))
    )
    (net (code "79") (name "unconnected-(D1A-PC13-Pad7)") (class "Default")
      (node (ref "D1") (pin "7") (pinfunction "PC13_7") (pintype "bidirectional"))
    )
    (net (code "80") (name "unconnected-(D1A-PD3-Pad84)") (class "Default")
      (node (ref "D1") (pin "84") (pinfunction "PD3_84") (pintype "bidirectional"))
    )
    (net (code "81") (name "unconnected-(D1A-PD4-Pad85)") (class "Default")
      (node (ref "D1") (pin "85") (pinfunction "PD4_85") (pintype "bidirectional"))
    )
    (net (code "82") (name "unconnected-(D1A-PD5-Pad86)") (class "Default")
      (node (ref "D1") (pin "86") (pinfunction "PD5_86") (pintype "bidirectional"))
    )
    (net (code "83") (name "unconnected-(D1A-PD6-Pad87)") (class "Default")
      (node (ref "D1") (pin "87") (pinfunction "PD6_87") (pintype "bidirectional"))
    )
    (net (code "84") (name "unconnected-(D1A-PD7-Pad88)") (class "Default")
      (node (ref "D1") (pin "88") (pinfunction "PD7_88") (pintype "bidirectional"))
    )
    (net (code "85") (name "unconnected-(D1A-PD8-Pad55)") (class "Default")
      (node (ref "D1") (pin "55") (pinfunction "PD8_55") (pintype "bidirectional"))
    )
    (net (code "86") (name "unconnected-(D1A-PD9-Pad56)") (class "Default")
      (node (ref "D1") (pin "56") (pinfunction "PD9_56") (pintype "bidirectional"))
    )
    (net (code "87") (name "unconnected-(D1A-PD10-Pad57)") (class "Default")
      (node (ref "D1") (pin "57") (pinfunction "PD10_57") (pintype "bidirectional"))
    )
    (net (code "88") (name "unconnected-(D1A-PD11-Pad58)") (class "Default")
      (node (ref "D1") (pin "58") (pinfunction "PD11_58") (pintype "bidirectional"))
    )
    (net (code "89") (name "unconnected-(D1A-PD12-Pad59)") (class "Default")
      (node (ref "D1") (pin "59") (pinfunction "PD12_59") (pintype "bidirectional"))
    )
    (net (code "90") (name "unconnected-(D1A-PD13-Pad60)") (class "Default")
      (node (ref "D1") (pin "60") (pinfunction "PD13_60") (pintype "bidirectional"))
    )
    (net (code "91") (name "unconnected-(D1A-PD14-Pad61)") (class "Default")
      (node (ref "D1") (pin "61") (pinfunction "PD14_61") (pintype "bidirectional"))
    )
    (net (code "92") (name "unconnected-(D1A-PD15-Pad62)") (class "Default")
      (node (ref "D1") (pin "62") (pinfunction "PD15_62") (pintype "bidirectional"))
    )
    (net (code "93") (name "unconnected-(D1A-PE0-Pad97)") (class "Default")
      (node (ref "D1") (pin "97") (pinfunction "PE0_97") (pintype "bidirectional"))
    )
    (net (code "94") (name "unconnected-(D1A-PE1-Pad98)") (class "Default")
      (node (ref "D1") (pin "98") (pinfunction "PE1_98") (pintype "bidirectional"))
    )
    (net (code "95") (name "unconnected-(D1A-PE2-Pad1)") (class "Default")
      (node (ref "D1") (pin "1") (pinfunction "PE2_1") (pintype "bidirectional"))
    )
    (net (code "96") (name "unconnected-(D1A-PE3-Pad2)") (class "Default")
      (node (ref "D1") (pin "2") (pinfunction "PE3_2") (pintype "bidirectional"))
    )
    (net (code "97") (name "unconnected-(D1A-PE4-Pad3)") (class "Default")
      (node (ref "D1") (pin "3") (pinfunction "PE4_3") (pintype "bidirectional"))
    )
    (net (code "98") (name "unconnected-(D1A-PE5-Pad4)") (class "Default")
      (node (ref "D1") (pin "4") (pinfunction "PE5_4") (pintype "bidirectional"))
    )
    (net (code "99") (name "unconnected-(D1A-PE6-Pad5)") (class "Default")
      (node (ref "D1") (pin "5") (pinfunction "PE6_5") (pintype "bidirectional"))
    )
    (net (code "100") (name "unconnected-(D1A-PE7-Pad38)") (class "Default")
      (node (ref "D1") (pin "38") (pinfunction "PE7_38") (pintype "bidirectional"))
    )
    (net (code "101") (name "unconnected-(D1A-PE8-Pad39)") (class "Default")
      (node (ref "D1") (pin "39") (pinfunction "PE8_39") (pintype "bidirectional"))
    )
    (net (code "102") (name "unconnected-(D1A-PE9-Pad40)") (class "Default")
      (node (ref "D1") (pin "40") (pinfunction "PE9_40") (pintype "bidirectional"))
    )
    (net (code "103") (name "unconnected-(D1A-PE10-Pad41)") (class "Default")
      (node (ref "D1") (pin "41") (pinfunction "PE10_41") (pintype "bidirectional"))
    )
    (net (code "104") (name "unconnected-(D1A-PE11-Pad42)") (class "Default")
      (node (ref "D1") (pin "42") (pinfunction "PE11_42") (pintype "bidirectional"))
    )
    (net (code "105") (name "unconnected-(D1A-PE12-Pad43)") (class "Default")
      (node (ref "D1") (pin "43") (pinfunction "PE12_43") (pintype "bidirectional"))
    )
    (net (code "106") (name "unconnected-(D1A-PE13-Pad44)") (class "Default")
      (node (ref "D1") (pin "44") (pinfunction "PE13_44") (pintype "bidirectional"))
    )
    (net (code "107") (name "unconnected-(D1A-PE14-Pad45)") (class "Default")
      (node (ref "D1") (pin "45") (pinfunction "PE14_45") (pintype "bidirectional"))
    )
    (net (code "108") (name "unconnected-(D1A-PE15-Pad46)") (class "Default")
      (node (ref "D1") (pin "46") (pinfunction "PE15_46") (pintype "bidirectional"))
    )
    (net (code "109") (name "unconnected-(D2-AIO0-Pad9)") (class "Default")
      (node (ref "D2") (pin "9") (pinfunction "AIO0_9") (pintype "bidirectional"))
    )
    (net (code "110") (name "unconnected-(D2-AIO1-Pad10)") (class "Default")
      (node (ref "D2") (pin "10") (pinfunction "AIO1_10") (pintype "bidirectional"))
    )
    (net (code "111") (name "unconnected-(D2-CLK-Pad19)") (class "Default")
      (node (ref "D2") (pin "19") (pinfunction "CLK_19") (pintype "input"))
    )
    (net (code "112") (name "unconnected-(D2-CSB-Pad16)") (class "Default")
      (node (ref "D2") (pin "16") (pinfunction "CSB_16") (pintype "input"))
    )
    (net (code "113") (name "unconnected-(D2-CTS-Pad3)") (class "Default")
      (node (ref "D2") (pin "3") (pinfunction "CTS_3") (pintype "passive"))
    )
    (net (code "114") (name "unconnected-(D2-GND-Pad21)") (class "Default")
      (node (ref "D2") (pin "21") (pinfunction "GND_21") (pintype "passive"))
    )
    (net (code "115") (name "unconnected-(D2-GND-Pad22)") (class "Default")
      (node (ref "D2") (pin "22") (pinfunction "GND_22") (pintype "passive"))
    )
    (net (code "116") (name "unconnected-(D2-MISO-Pad18)") (class "Default")
      (node (ref "D2") (pin "18") (pinfunction "MISO_18") (pintype "output"))
    )
    (net (code "117") (name "unconnected-(D2-MOSI-Pad17)") (class "Default")
      (node (ref "D2") (pin "17") (pinfunction "MOSI_17") (pintype "input"))
    )
    (net (code "118") (name "unconnected-(D2-NC-Pad14)") (class "Default")
      (node (ref "D2") (pin "14") (pinfunction "NC_14") (pintype "passive"))
    )
    (net (code "119") (name "unconnected-(D2-PCM_CLK-Pad5)") (class "Default")
      (node (ref "D2") (pin "5") (pinfunction "PCM_CLK_5") (pintype "input"))
    )
    (net (code "120") (name "unconnected-(D2-PCM_IN-Pad7)") (class "Default")
      (node (ref "D2") (pin "7") (pinfunction "PCM_IN_7") (pintype "input"))
    )
    (net (code "121") (name "unconnected-(D2-PCM_OUT-Pad6)") (class "Default")
      (node (ref "D2") (pin "6") (pinfunction "PCM_OUT_6") (pintype "output"))
    )
    (net (code "122") (name "unconnected-(D2-PCM_SYNC-Pad8)") (class "Default")
      (node (ref "D2") (pin "8") (pinfunction "PCM_SYNC_8") (pintype "bidirectional"))
    )
    (net (code "123") (name "unconnected-(D2-PIO0-Pad23)") (class "Default")
      (node (ref "D2") (pin "23") (pinfunction "PIO0_23") (pintype "bidirectional"))
    )
    (net (code "124") (name "unconnected-(D2-PIO1-Pad24)") (class "Default")
      (node (ref "D2") (pin "24") (pinfunction "PIO1_24") (pintype "bidirectional"))
    )
    (net (code "125") (name "unconnected-(D2-PIO2-Pad25)") (class "Default")
      (node (ref "D2") (pin "25") (pinfunction "PIO2_25") (pintype "bidirectional"))
    )
    (net (code "126") (name "unconnected-(D2-PIO4-Pad27)") (class "Default")
      (node (ref "D2") (pin "27") (pinfunction "PIO4_27") (pintype "bidirectional"))
    )
    (net (code "127") (name "unconnected-(D2-PIO5-Pad28)") (class "Default")
      (node (ref "D2") (pin "28") (pinfunction "PIO5_28") (pintype "bidirectional"))
    )
    (net (code "128") (name "unconnected-(D2-PIO6-Pad29)") (class "Default")
      (node (ref "D2") (pin "29") (pinfunction "PIO6_29") (pintype "bidirectional"))
    )
    (net (code "129") (name "unconnected-(D2-PIO7-Pad30)") (class "Default")
      (node (ref "D2") (pin "30") (pinfunction "PIO7_30") (pintype "bidirectional"))
    )
    (net (code "130") (name "unconnected-(D2-PIO8-Pad31)") (class "Default")
      (node (ref "D2") (pin "31") (pinfunction "PIO8_31") (pintype "bidirectional"))
    )
    (net (code "131") (name "unconnected-(D2-PIO10-Pad33)") (class "Default")
      (node (ref "D2") (pin "33") (pinfunction "PIO10_33") (pintype "bidirectional"))
    )
    (net (code "132") (name "unconnected-(D2-PIO11-Pad34)") (class "Default")
      (node (ref "D2") (pin "34") (pinfunction "PIO11_34") (pintype "bidirectional"))
    )
    (net (code "133") (name "unconnected-(D2-RESET-Pad11)") (class "Default")
      (node (ref "D2") (pin "11") (pinfunction "RESET_11") (pintype "input"))
    )
    (net (code "134") (name "unconnected-(D2-RTS-Pad4)") (class "Default")
      (node (ref "D2") (pin "4") (pinfunction "RTS_4") (pintype "passive"))
    )
    (net (code "135") (name "unconnected-(D2-USB_D+-Pad20)") (class "Default")
      (node (ref "D2") (pin "20") (pinfunction "USB_D+_20") (pintype "output"))
    )
    (net (code "136") (name "unconnected-(D2-USB_D--Pad15)") (class "Default")
      (node (ref "D2") (pin "15") (pinfunction "USB_D-_15") (pintype "bidirectional"))
    )
    (net (code "137") (name "unconnected-(D3-ESD1-Pad4)") (class "Default")
      (node (ref "D3") (pin "4") (pinfunction "ESD1_4") (pintype "passive"))
    )
    (net (code "138") (name "unconnected-(D3-ESD1-Pad13)") (class "Default")
      (node (ref "D3") (pin "13") (pinfunction "ESD1_13") (pintype "passive"))
    )
    (net (code "139") (name "unconnected-(D3-ESD3-Pad5)") (class "Default")
      (node (ref "D3") (pin "5") (pinfunction "ESD3_5") (pintype "passive"))
    )
    (net (code "140") (name "unconnected-(D5-VREF-Pad5)") (class "Default")
      (node (ref "D5") (pin "5") (pinfunction "VREF_5") (pintype "passive"))
    )
  )
)
